# BoardAttiny.net
KiCad netlist of a schematic drawn in EAGLE
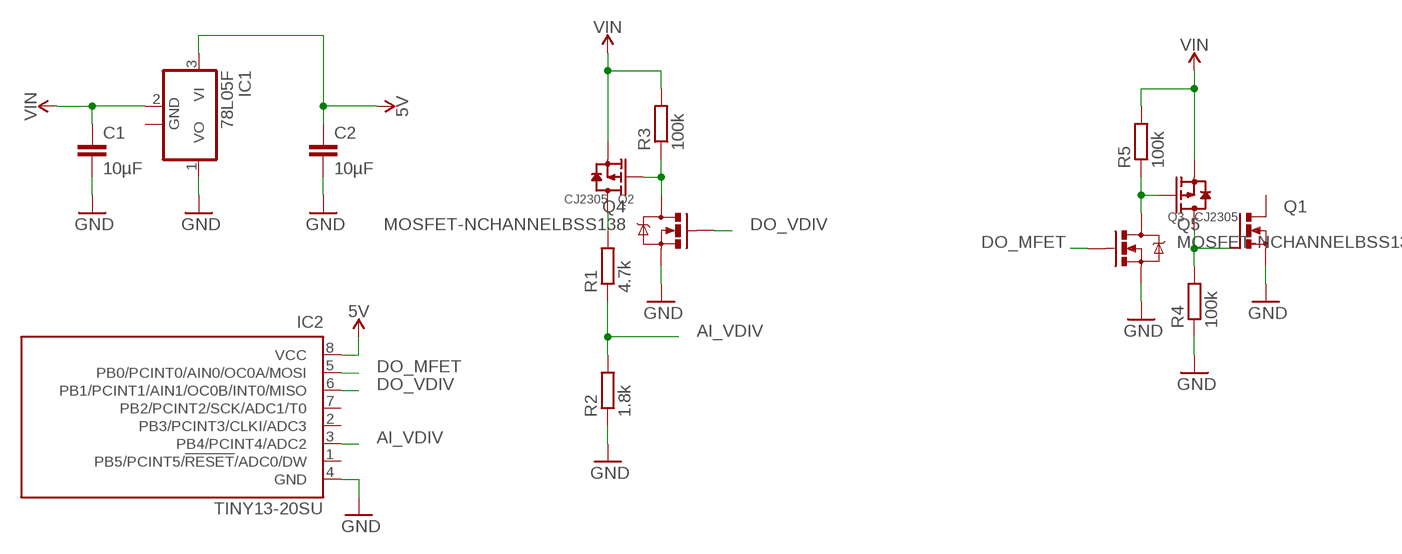
[diagram p0: schematic, sheet 1]

(export (version "E")
  (design (tool "Eeschema 10.0.6"))
  (components
    (comp (ref "C1")
      (value "10µF")
      (footprint "eagle-import:C0805")
      (libsource (lib "eagle-import") (part "C-EUC0805"))
    )
    (comp (ref "C2")
      (value "10µF")
      (footprint "eagle-import:C0805")
      (libsource (lib "eagle-import") (part "C-EUC0805"))
    )
    (comp (ref "IC1")
      (value "78L05F")
      (footprint "eagle-import:SOT89")
      (libsource (lib "eagle-import") (part "78LF05"))
    )
    (comp (ref "IC2")
      (value "TINY13-20SU")
      (footprint "eagle-import:8S2")
      (fields (field (name "MPN") "ATTINY13-20SU"))
      (libsource (lib "eagle-import") (part "TINY13SU-20"))
    )
    (comp (ref "Q1")
      (value "PMOSFET_NTO220BH")
      (footprint "eagle-import:TO220BH")
      (libsource (lib "eagle-import") (part "PMOSFET_NTO220BH"))
    )
    (comp (ref "Q2")
      (value "CJ2305")
      (footprint "eagle-import:SOT-23")
      (libsource (lib "eagle-import") (part "SMD-MOSFET-P-CH-8V-4.1A-CJ2305(SOT-23)"))
    )
    (comp (ref "Q3")
      (value "CJ2305")
      (footprint "eagle-import:SOT-23")
      (libsource (lib "eagle-import") (part "SMD-MOSFET-P-CH-8V-4.1A-CJ2305(SOT-23)"))
    )
    (comp (ref "Q4")
      (value "MOSFET-NCHANNELBSS138")
      (footprint "eagle-import:SOT23")
      (libsource (lib "eagle-import") (part "MOSFET-NCHANNELBSS138"))
    )
    (comp (ref "Q5")
      (value "MOSFET-NCHANNELBSS138")
      (footprint "eagle-import:SOT23")
      (libsource (lib "eagle-import") (part "MOSFET-NCHANNELBSS138"))
    )
    (comp (ref "R1")
      (value "4.7k")
      (footprint "eagle-import:R0805")
      (libsource (lib "eagle-import") (part "R-EU_R0805"))
    )
    (comp (ref "R2")
      (value "1.8k")
      (footprint "eagle-import:R0805")
      (libsource (lib "eagle-import") (part "R-EU_R0805"))
    )
    (comp (ref "R3")
      (value "100k")
      (footprint "eagle-import:R0805")
      (libsource (lib "eagle-import") (part "R-EU_R0805"))
    )
    (comp (ref "R4")
      (value "100k")
      (footprint "eagle-import:R0805")
      (libsource (lib "eagle-import") (part "R-EU_R0805"))
    )
    (comp (ref "R5")
      (value "100k")
      (footprint "eagle-import:R0805")
      (libsource (lib "eagle-import") (part "R-EU_R0805"))
    )
  )
  (nets
    (net (code "1") (name "/AI_VDIV") (class "Default")
      (node (ref "IC2") (pin "3") (pinfunction "PB4/PCINT4/ADC2_3") (pintype "bidirectional"))
      (node (ref "R1") (pin "1") (pinfunction "1_1") (pintype "passive"))
      (node (ref "R2") (pin "2") (pinfunction "2_2") (pintype "passive"))
    )
    (net (code "2") (name "/DO_MFET") (class "Default")
      (node (ref "IC2") (pin "5") (pinfunction "PB0/PCINT0/AIN0/OC0A/MOSI_5") (pintype "bidirectional"))
      (node (ref "Q5") (pin "1") (pinfunction "G_1") (pintype "passive"))
    )
    (net (code "3") (name "/DO_VDIV") (class "Default")
      (node (ref "IC2") (pin "6") (pinfunction "PB1/PCINT1/AIN1/OC0B/INT0/MISO_6") (pintype "bidirectional"))
      (node (ref "Q4") (pin "1") (pinfunction "G_1") (pintype "passive"))
    )
    (net (code "4") (name "5V") (class "Default")
      (node (ref "C2") (pin "1") (pinfunction "1_1") (pintype "passive"))
      (node (ref "IC1") (pin "3") (pinfunction "VI_3") (pintype "input"))
      (node (ref "IC2") (pin "8") (pinfunction "VCC_8") (pintype "power_in"))
    )
    (net (code "5") (name "GND") (class "Default")
      (node (ref "C1") (pin "2") (pinfunction "2_2") (pintype "passive"))
      (node (ref "C2") (pin "2") (pinfunction "2_2") (pintype "passive"))
      (node (ref "IC1") (pin "1") (pinfunction "VO_1") (pintype "passive"))
      (node (ref "IC2") (pin "4") (pinfunction "GND_4") (pintype "power_in"))
      (node (ref "Q1") (pin "S") (pinfunction "S_S") (pintype "passive"))
      (node (ref "Q4") (pin "2") (pinfunction "S_2") (pintype "passive"))
      (node (ref "Q5") (pin "2") (pinfunction "S_2") (pintype "passive"))
      (node (ref "R2") (pin "1") (pinfunction "1_1") (pintype "passive"))
      (node (ref "R4") (pin "1") (pinfunction "1_1") (pintype "passive"))
    )
    (net (code "6") (name "Net-(Q2-D)") (class "Default")
      (node (ref "Q2") (pin "3") (pinfunction "D_3") (pintype "passive"))
      (node (ref "R1") (pin "2") (pinfunction "2_2") (pintype "passive"))
    )
    (net (code "7") (name "Net-(Q2-G)") (class "Default")
      (node (ref "Q2") (pin "1") (pinfunction "G_1") (pintype "passive"))
      (node (ref "Q4") (pin "3") (pinfunction "D_3") (pintype "passive"))
      (node (ref "R3") (pin "1") (pinfunction "1_1") (pintype "passive"))
    )
    (net (code "8") (name "Net-(Q3-D)") (class "Default")
      (node (ref "Q1") (pin "G") (pinfunction "G_G") (pintype "passive"))
      (node (ref "Q3") (pin "3") (pinfunction "D_3") (pintype "passive"))
      (node (ref "R4") (pin "2") (pinfunction "2_2") (pintype "passive"))
    )
    (net (code "9") (name "Net-(Q3-G)") (class "Default")
      (node (ref "Q3") (pin "1") (pinfunction "G_1") (pintype "passive"))
      (node (ref "Q5") (pin "3") (pinfunction "D_3") (pintype "passive"))
      (node (ref "R5") (pin "1") (pinfunction "1_1") (pintype "passive"))
    )
    (net (code "10") (name "VIN") (class "Default")
      (node (ref "C1") (pin "1") (pinfunction "1_1") (pintype "passive"))
      (node (ref "IC1") (pin "2") (pinfunction "GND_2") (pintype "passive"))
      (node (ref "Q2") (pin "2") (pinfunction "S_2") (pintype "passive"))
      (node (ref "Q3") (pin "2") (pinfunction "S_2") (pintype "passive"))
      (node (ref "R3") (pin "2") (pinfunction "2_2") (pintype "passive"))
      (node (ref "R5") (pin "2") (pinfunction "2_2") (pintype "passive"))
    )
    (net (code "11") (name "unconnected-(IC1-GND-Pad2@1)") (class "Default")
      (node (ref "IC1") (pin "2@1") (pinfunction "GND_2@1") (pintype "passive"))
    )
    (net (code "12") (name "unconnected-(IC2-PB2{slash}PCINT2{slash}SCK{slash}ADC1{slash}T0-Pad7)") (class "Default")
      (node (ref "IC2") (pin "7") (pinfunction "PB2/PCINT2/SCK/ADC1/T0_7") (pintype "bidirectional"))
    )
    (net (code "13") (name "unconnected-(IC2-PB3{slash}PCINT3{slash}CLKI{slash}ADC3-Pad2)") (class "Default")
      (node (ref "IC2") (pin "2") (pinfunction "PB3/PCINT3/CLKI/ADC3_2") (pintype "bidirectional"))
    )
    (net (code "14") (name "unconnected-(IC2-PB5{slash}PCINT5{slash}~{RESET}{slash}ADC0{slash}DW-Pad1)") (class "Default")
      (node (ref "IC2") (pin "1") (pinfunction "PB5/PCINT5/~{RESET}/ADC0/DW_1") (pintype "bidirectional"))
    )
    (net (code "15") (name "unconnected-(Q1-PadD)") (class "Default")
      (node (ref "Q1") (pin "D") (pinfunction "D_D") (pintype "passive"))
    )
  )
)
